# Keypad_Board.net
KiCad netlist of a schematic drawn in EAGLE
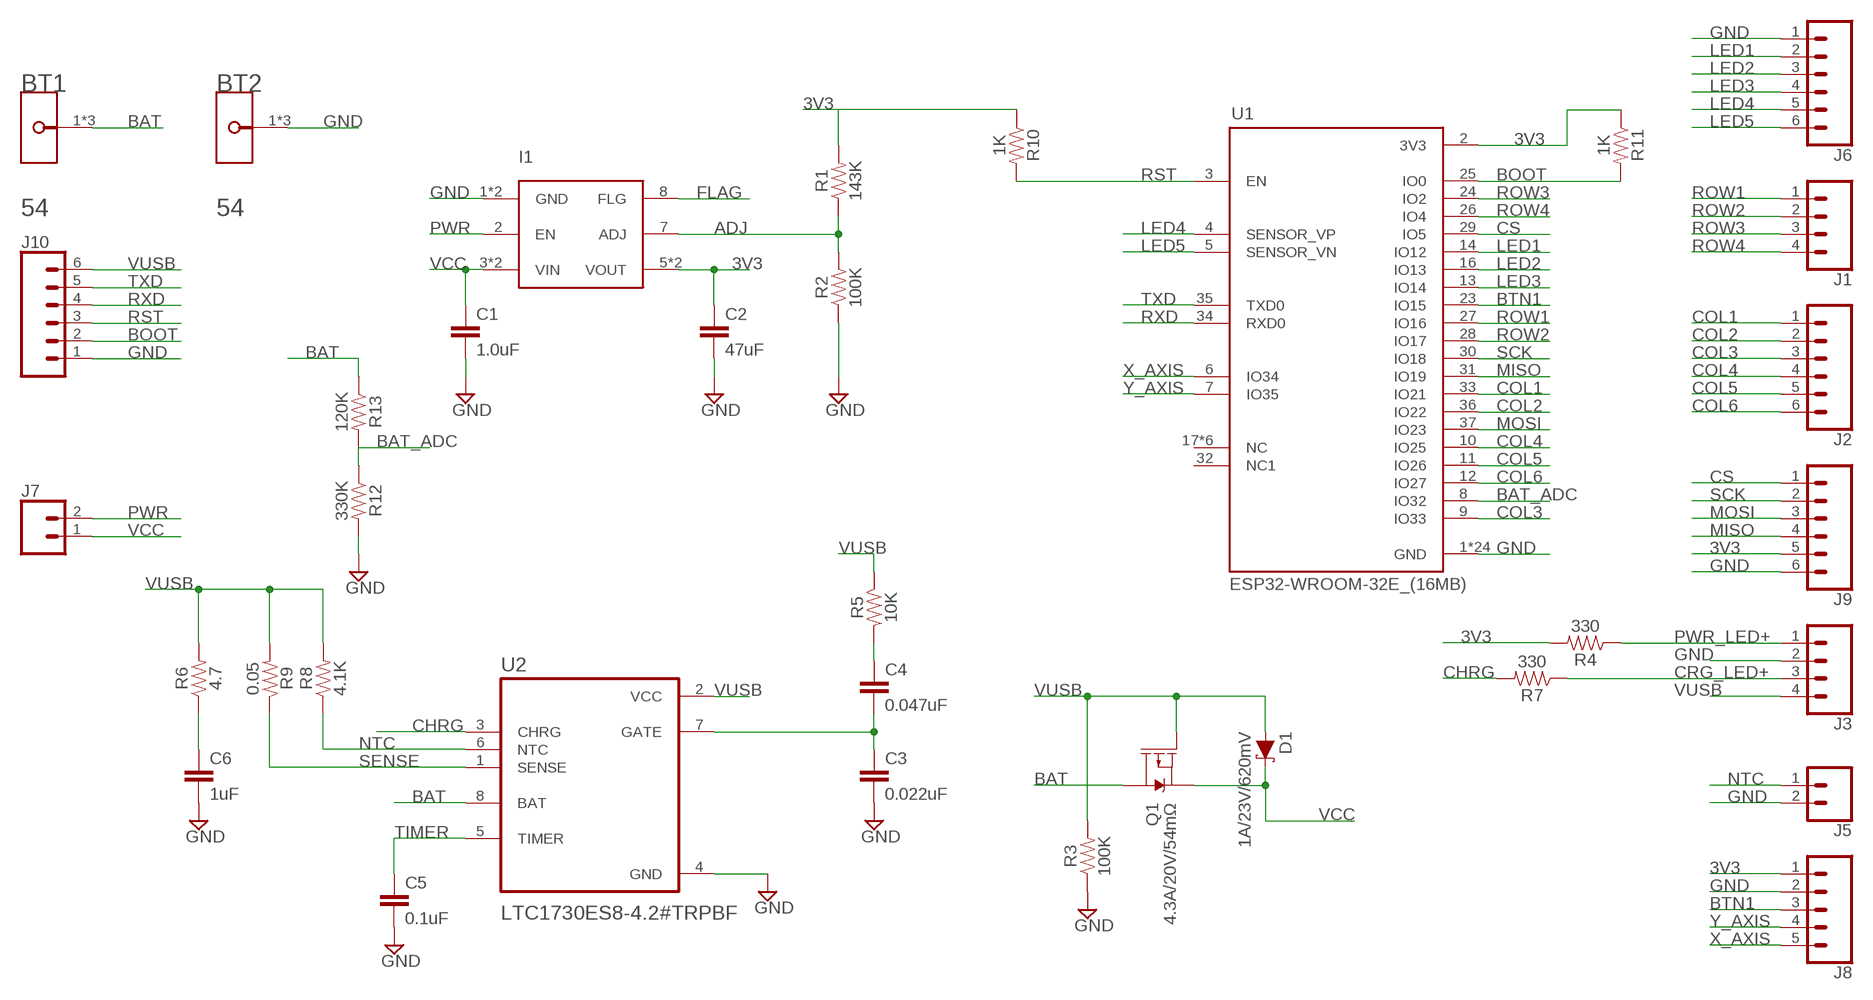
[diagram p0: schematic, sheet 1]

(export (version "E")
  (design (tool "Eeschema 10.0.6"))
  (components
    (comp (ref "BT1")
      (value "KEYSTONE_54KEYSTONE_54_0_0")
      (footprint "eagle-import:KEYSTONE_54_0")
      (fields
        (field (name "DIGIKEY_PART_NUMBER") "36-54-ND")
        (field (name "MF") "Keystone")
        (field (name "MOUSER_PART_NUMBER") "534-54")
      )
      (libsource (lib "eagle-import") (part "KEYSTONE_54KEYSTONE_54_0_0"))
    )
    (comp (ref "BT2")
      (value "KEYSTONE_54KEYSTONE_54_0_0")
      (footprint "eagle-import:KEYSTONE_54_0")
      (fields
        (field (name "DIGIKEY_PART_NUMBER") "36-54-ND")
        (field (name "MF") "Keystone")
        (field (name "MOUSER_PART_NUMBER") "534-54")
      )
      (libsource (lib "eagle-import") (part "KEYSTONE_54KEYSTONE_54_0_0"))
    )
    (comp (ref "C1")
      (value "1.0uF")
      (footprint "eagle-import:1206")
      (libsource (lib "eagle-import") (part "1.0UF-1206-50V-10%"))
    )
    (comp (ref "C2")
      (value "47uF")
      (footprint "eagle-import:1206")
      (libsource (lib "eagle-import") (part "4.7UF-1206-16V-(+80/-20%)"))
    )
    (comp (ref "C3")
      (value "0.022uF")
      (footprint "eagle-import:0603")
      (libsource (lib "eagle-import") (part "0.22UF-0603-50V-(-20/+80%)"))
    )
    (comp (ref "C4")
      (value "0.047uF")
      (footprint "eagle-import:0603")
      (libsource (lib "eagle-import") (part "0.22UF-0603-50V-(-20/+80%)"))
    )
    (comp (ref "C5")
      (value "0.1uF")
      (footprint "eagle-import:0603")
      (libsource (lib "eagle-import") (part "0.22UF-0603-50V-(-20/+80%)"))
    )
    (comp (ref "C6")
      (value "1uF")
      (footprint "eagle-import:0603")
      (libsource (lib "eagle-import") (part "0.22UF-0603-50V-(-20/+80%)"))
    )
    (comp (ref "D1")
      (value "1A/23V/620mV")
      (footprint "eagle-import:SOD-323")
      (libsource (lib "eagle-import") (part "DIODE-SCHOTTKY-BAT20J"))
    )
    (comp (ref "I1")
      (value "MIC37303")
      (footprint "eagle-import:SOIC8")
      (libsource (lib "eagle-import") (part "MIC37303"))
    )
    (comp (ref "J1")
      (value "CONN_04")
      (footprint "eagle-import:1X04")
      (libsource (lib "eagle-import") (part "CONN_04"))
    )
    (comp (ref "J2")
      (value "CONN_06LOCK")
      (footprint "eagle-import:1X06_LOCK")
      (libsource (lib "eagle-import") (part "CONN_06LOCK"))
    )
    (comp (ref "J3")
      (value "CONN_04")
      (footprint "eagle-import:1X04")
      (libsource (lib "eagle-import") (part "CONN_04"))
    )
    (comp (ref "J5")
      (value "CONN_02")
      (footprint "eagle-import:1X02")
      (libsource (lib "eagle-import") (part "CONN_02"))
    )
    (comp (ref "J6")
      (value "CONN_06LOCK")
      (footprint "eagle-import:1X06_LOCK")
      (libsource (lib "eagle-import") (part "CONN_06LOCK"))
    )
    (comp (ref "J7")
      (value "CONN_02")
      (footprint "eagle-import:1X02")
      (libsource (lib "eagle-import") (part "CONN_02"))
    )
    (comp (ref "J8")
      (value "CONN_05")
      (footprint "eagle-import:1X05")
      (libsource (lib "eagle-import") (part "CONN_05"))
    )
    (comp (ref "J9")
      (value "CONN_06LOCK")
      (footprint "eagle-import:1X06_LOCK")
      (libsource (lib "eagle-import") (part "CONN_06LOCK"))
    )
    (comp (ref "J10")
      (value "CONN_06LOCK")
      (footprint "eagle-import:1X06_LOCK")
      (libsource (lib "eagle-import") (part "CONN_06LOCK"))
    )
    (comp (ref "Q1")
      (value "4.3A/20V/54mΩ")
      (footprint "eagle-import:SOT23-3")
      (libsource (lib "eagle-import") (part "MOSFET_PCH-IRLML2244"))
    )
    (comp (ref "R1")
      (value "143K")
      (footprint "eagle-import:1206")
      (libsource (lib "eagle-import") (part "RESISTOR1206"))
    )
    (comp (ref "R2")
      (value "100K")
      (footprint "eagle-import:1206")
      (libsource (lib "eagle-import") (part "RESISTOR1206"))
    )
    (comp (ref "R3")
      (value "100K")
      (footprint "eagle-import:1206")
      (libsource (lib "eagle-import") (part "RESISTOR1206"))
    )
    (comp (ref "R4")
      (value "330")
      (footprint "eagle-import:0805")
      (libsource (lib "eagle-import") (part "0.22OHM-0805-1/4W-1%"))
    )
    (comp (ref "R5")
      (value "10K")
      (footprint "eagle-import:0805")
      (libsource (lib "eagle-import") (part "0.22OHM-0805-1/4W-1%"))
    )
    (comp (ref "R6")
      (value "4.7")
      (footprint "eagle-import:0603")
      (libsource (lib "eagle-import") (part "0.05OHM-0603-1/5W-1%"))
    )
    (comp (ref "R7")
      (value "330")
      (footprint "eagle-import:0805")
      (libsource (lib "eagle-import") (part "0.22OHM-0805-1/4W-1%"))
    )
    (comp (ref "R8")
      (value "4.1K")
      (footprint "eagle-import:0603")
      (libsource (lib "eagle-import") (part "0.05OHM-0603-1/5W-1%"))
    )
    (comp (ref "R9")
      (value "0.05")
      (footprint "eagle-import:0603")
      (libsource (lib "eagle-import") (part "0.05OHM-0603-1/5W-1%"))
    )
    (comp (ref "R10")
      (value "1K")
      (footprint "eagle-import:0805")
      (libsource (lib "eagle-import") (part "0.22OHM-0805-1/4W-1%"))
    )
    (comp (ref "R11")
      (value "1K")
      (footprint "eagle-import:0805")
      (libsource (lib "eagle-import") (part "0.22OHM-0805-1/4W-1%"))
    )
    (comp (ref "R12")
      (value "330K")
      (footprint "eagle-import:0805")
      (libsource (lib "eagle-import") (part "0.22OHM-0805-1/4W-1%"))
    )
    (comp (ref "R13")
      (value "120K")
      (footprint "eagle-import:0805")
      (libsource (lib "eagle-import") (part "0.22OHM-0805-1/4W-1%"))
    )
    (comp (ref "U1")
      (value "ESP32-WROOM-32E_(16MB)")
      (footprint "eagle-import:MODULE_ESP32-WROOM-32E_(16MB)")
      (fields (field (name "MF") "Espressif Systems") (field (name "MP") "ESP32-WROOM-32E (16MB)"))
      (libsource (lib "eagle-import") (part "ESP32-WROOM-32E_(16MB)"))
    )
    (comp (ref "U2")
      (value "LTC1730ES8-4.2#TRPBF")
      (footprint "eagle-import:SO-8_S")
      (fields (field (name "MF") "Analog Devices"))
      (libsource (lib "eagle-import") (part "LTC1730ES8-4.2#TRPBF"))
    )
  )
  (nets
    (net (code "1") (name "/3V3") (class "Default")
      (node (ref "C2") (pin "1") (pinfunction "1_1") (pintype "passive"))
      (node (ref "I1") (pin "5") (pinfunction "VOUT_5") (pintype "output"))
      (node (ref "I1") (pin "6") (pinfunction "VOUT_6") (pintype "output"))
      (node (ref "J8") (pin "1") (pinfunction "1_1") (pintype "passive"))
      (node (ref "J9") (pin "5") (pinfunction "5_5") (pintype "passive"))
      (node (ref "R1") (pin "2") (pinfunction "2_2") (pintype "passive"))
      (node (ref "R10") (pin "1") (pinfunction "1_1") (pintype "passive"))
      (node (ref "R11") (pin "1") (pinfunction "1_1") (pintype "passive"))
      (node (ref "R4") (pin "2") (pinfunction "2_2") (pintype "passive"))
      (node (ref "U1") (pin "2") (pinfunction "3V3_2") (pintype "power_in"))
    )
    (net (code "2") (name "/ADJ") (class "Default")
      (node (ref "I1") (pin "7") (pinfunction "ADJ_7") (pintype "input"))
      (node (ref "R1") (pin "1") (pinfunction "1_1") (pintype "passive"))
      (node (ref "R2") (pin "2") (pinfunction "2_2") (pintype "passive"))
    )
    (net (code "3") (name "/BAT") (class "Default")
      (node (ref "BT1") (pin "1") (pinfunction "1_1") (pintype "power_in"))
      (node (ref "BT1") (pin "1-2") (pinfunction "1_1-2") (pintype "power_in"))
      (node (ref "BT1") (pin "1-3") (pinfunction "1_1-3") (pintype "power_in"))
      (node (ref "Q1") (pin "3") (pinfunction "D_3") (pintype "bidirectional"))
      (node (ref "R13") (pin "1") (pinfunction "1_1") (pintype "passive"))
      (node (ref "U2") (pin "8") (pinfunction "BAT_8") (pintype "bidirectional"))
    )
    (net (code "4") (name "/BAT_ADC") (class "Default")
      (node (ref "R12") (pin "1") (pinfunction "1_1") (pintype "passive"))
      (node (ref "R13") (pin "2") (pinfunction "2_2") (pintype "passive"))
      (node (ref "U1") (pin "8") (pinfunction "IO32_8") (pintype "bidirectional"))
    )
    (net (code "5") (name "/BOOT") (class "Default")
      (node (ref "J10") (pin "2") (pinfunction "2_2") (pintype "passive"))
      (node (ref "R11") (pin "2") (pinfunction "2_2") (pintype "passive"))
      (node (ref "U1") (pin "25") (pinfunction "IO0_25") (pintype "bidirectional"))
    )
    (net (code "6") (name "/BTN1") (class "Default")
      (node (ref "J8") (pin "3") (pinfunction "3_3") (pintype "passive"))
      (node (ref "U1") (pin "23") (pinfunction "IO15_23") (pintype "bidirectional"))
    )
    (net (code "7") (name "/CHRG") (class "Default")
      (node (ref "R7") (pin "2") (pinfunction "2_2") (pintype "passive"))
      (node (ref "U2") (pin "3") (pinfunction "CHRG_3") (pintype "input"))
    )
    (net (code "8") (name "/COL1") (class "Default")
      (node (ref "J2") (pin "1") (pinfunction "1_1") (pintype "passive"))
      (node (ref "U1") (pin "33") (pinfunction "IO21_33") (pintype "bidirectional"))
    )
    (net (code "9") (name "/COL2") (class "Default")
      (node (ref "J2") (pin "2") (pinfunction "2_2") (pintype "passive"))
      (node (ref "U1") (pin "36") (pinfunction "IO22_36") (pintype "bidirectional"))
    )
    (net (code "10") (name "/COL3") (class "Default")
      (node (ref "J2") (pin "3") (pinfunction "3_3") (pintype "passive"))
      (node (ref "U1") (pin "9") (pinfunction "IO33_9") (pintype "bidirectional"))
    )
    (net (code "11") (name "/COL4") (class "Default")
      (node (ref "J2") (pin "4") (pinfunction "4_4") (pintype "passive"))
      (node (ref "U1") (pin "10") (pinfunction "IO25_10") (pintype "bidirectional"))
    )
    (net (code "12") (name "/COL5") (class "Default")
      (node (ref "J2") (pin "5") (pinfunction "5_5") (pintype "passive"))
      (node (ref "U1") (pin "11") (pinfunction "IO26_11") (pintype "bidirectional"))
    )
    (net (code "13") (name "/COL6") (class "Default")
      (node (ref "J2") (pin "6") (pinfunction "6_6") (pintype "passive"))
      (node (ref "U1") (pin "12") (pinfunction "IO27_12") (pintype "bidirectional"))
    )
    (net (code "14") (name "/CRG_LED+") (class "Default")
      (node (ref "J3") (pin "3") (pinfunction "3_3") (pintype "passive"))
      (node (ref "R7") (pin "1") (pinfunction "1_1") (pintype "passive"))
    )
    (net (code "15") (name "/CS") (class "Default")
      (node (ref "J9") (pin "1") (pinfunction "1_1") (pintype "passive"))
      (node (ref "U1") (pin "29") (pinfunction "IO5_29") (pintype "bidirectional"))
    )
    (net (code "16") (name "/FLAG") (class "Default")
      (node (ref "I1") (pin "8") (pinfunction "FLG_8") (pintype "output"))
    )
    (net (code "17") (name "/LED1") (class "Default")
      (node (ref "J6") (pin "2") (pinfunction "2_2") (pintype "passive"))
      (node (ref "U1") (pin "14") (pinfunction "IO12_14") (pintype "bidirectional"))
    )
    (net (code "18") (name "/LED2") (class "Default")
      (node (ref "J6") (pin "3") (pinfunction "3_3") (pintype "passive"))
      (node (ref "U1") (pin "16") (pinfunction "IO13_16") (pintype "bidirectional"))
    )
    (net (code "19") (name "/LED3") (class "Default")
      (node (ref "J6") (pin "4") (pinfunction "4_4") (pintype "passive"))
      (node (ref "U1") (pin "13") (pinfunction "IO14_13") (pintype "bidirectional"))
    )
    (net (code "20") (name "/LED4") (class "Default")
      (node (ref "J6") (pin "5") (pinfunction "5_5") (pintype "passive"))
      (node (ref "U1") (pin "4") (pinfunction "SENSOR_VP_4") (pintype "input"))
    )
    (net (code "21") (name "/LED5") (class "Default")
      (node (ref "J6") (pin "6") (pinfunction "6_6") (pintype "passive"))
      (node (ref "U1") (pin "5") (pinfunction "SENSOR_VN_5") (pintype "input"))
    )
    (net (code "22") (name "/MISO") (class "Default")
      (node (ref "J9") (pin "4") (pinfunction "4_4") (pintype "passive"))
      (node (ref "U1") (pin "31") (pinfunction "IO19_31") (pintype "bidirectional"))
    )
    (net (code "23") (name "/MOSI") (class "Default")
      (node (ref "J9") (pin "3") (pinfunction "3_3") (pintype "passive"))
      (node (ref "U1") (pin "37") (pinfunction "IO23_37") (pintype "bidirectional"))
    )
    (net (code "24") (name "/NTC") (class "Default")
      (node (ref "J5") (pin "1") (pinfunction "1_1") (pintype "passive"))
      (node (ref "R8") (pin "1") (pinfunction "1_1") (pintype "passive"))
      (node (ref "U2") (pin "6") (pinfunction "NTC_6") (pintype "input"))
    )
    (net (code "25") (name "/PWR") (class "Default")
      (node (ref "I1") (pin "2") (pinfunction "EN_2") (pintype "input"))
      (node (ref "J7") (pin "2") (pinfunction "2_2") (pintype "passive"))
    )
    (net (code "26") (name "/PWR_LED+") (class "Default")
      (node (ref "J3") (pin "1") (pinfunction "1_1") (pintype "passive"))
      (node (ref "R4") (pin "1") (pinfunction "1_1") (pintype "passive"))
    )
    (net (code "27") (name "/ROW1") (class "Default")
      (node (ref "J1") (pin "1") (pinfunction "1_1") (pintype "passive"))
      (node (ref "U1") (pin "27") (pinfunction "IO16_27") (pintype "bidirectional"))
    )
    (net (code "28") (name "/ROW2") (class "Default")
      (node (ref "J1") (pin "2") (pinfunction "2_2") (pintype "passive"))
      (node (ref "U1") (pin "28") (pinfunction "IO17_28") (pintype "bidirectional"))
    )
    (net (code "29") (name "/ROW3") (class "Default")
      (node (ref "J1") (pin "3") (pinfunction "3_3") (pintype "passive"))
      (node (ref "U1") (pin "24") (pinfunction "IO2_24") (pintype "bidirectional"))
    )
    (net (code "30") (name "/ROW4") (class "Default")
      (node (ref "J1") (pin "4") (pinfunction "4_4") (pintype "passive"))
      (node (ref "U1") (pin "26") (pinfunction "IO4_26") (pintype "bidirectional"))
    )
    (net (code "31") (name "/RST") (class "Default")
      (node (ref "J10") (pin "3") (pinfunction "3_3") (pintype "passive"))
      (node (ref "R10") (pin "2") (pinfunction "2_2") (pintype "passive"))
      (node (ref "U1") (pin "3") (pinfunction "EN_3") (pintype "input"))
    )
    (net (code "32") (name "/RXD") (class "Default")
      (node (ref "J10") (pin "4") (pinfunction "4_4") (pintype "passive"))
      (node (ref "U1") (pin "34") (pinfunction "RXD0_34") (pintype "bidirectional"))
    )
    (net (code "33") (name "/SCK") (class "Default")
      (node (ref "J9") (pin "2") (pinfunction "2_2") (pintype "passive"))
      (node (ref "U1") (pin "30") (pinfunction "IO18_30") (pintype "bidirectional"))
    )
    (net (code "34") (name "/SENSE") (class "Default")
      (node (ref "R9") (pin "1") (pinfunction "1_1") (pintype "passive"))
      (node (ref "U2") (pin "1") (pinfunction "SENSE_1") (pintype "input"))
    )
    (net (code "35") (name "/TIMER") (class "Default")
      (node (ref "C5") (pin "1") (pinfunction "1_1") (pintype "passive"))
      (node (ref "U2") (pin "5") (pinfunction "TIMER_5") (pintype "bidirectional"))
    )
    (net (code "36") (name "/TXD") (class "Default")
      (node (ref "J10") (pin "5") (pinfunction "5_5") (pintype "passive"))
      (node (ref "U1") (pin "35") (pinfunction "TXD0_35") (pintype "bidirectional"))
    )
    (net (code "37") (name "/VCC") (class "Default")
      (node (ref "C1") (pin "1") (pinfunction "1_1") (pintype "passive"))
      (node (ref "D1") (pin "C") (pinfunction "C_C") (pintype "passive"))
      (node (ref "I1") (pin "3") (pinfunction "VIN_3") (pintype "input"))
      (node (ref "I1") (pin "4") (pinfunction "VIN_4") (pintype "input"))
      (node (ref "J7") (pin "1") (pinfunction "1_1") (pintype "passive"))
      (node (ref "Q1") (pin "2") (pinfunction "S_2") (pintype "bidirectional"))
    )
    (net (code "38") (name "/VUSB") (class "Default")
      (node (ref "D1") (pin "A") (pinfunction "A_A") (pintype "passive"))
      (node (ref "J10") (pin "6") (pinfunction "6_6") (pintype "passive"))
      (node (ref "J3") (pin "4") (pinfunction "4_4") (pintype "passive"))
      (node (ref "Q1") (pin "1") (pinfunction "G_1") (pintype "bidirectional"))
      (node (ref "R3") (pin "2") (pinfunction "2_2") (pintype "passive"))
      (node (ref "R5") (pin "1") (pinfunction "1_1") (pintype "passive"))
      (node (ref "R6") (pin "2") (pinfunction "2_2") (pintype "passive"))
      (node (ref "R8") (pin "2") (pinfunction "2_2") (pintype "passive"))
      (node (ref "R9") (pin "2") (pinfunction "2_2") (pintype "passive"))
      (node (ref "U2") (pin "2") (pinfunction "VCC_2") (pintype "power_in"))
    )
    (net (code "39") (name "/X_AXIS") (class "Default")
      (node (ref "J8") (pin "5") (pinfunction "5_5") (pintype "passive"))
      (node (ref "U1") (pin "6") (pinfunction "IO34_6") (pintype "input"))
    )
    (net (code "40") (name "/Y_AXIS") (class "Default")
      (node (ref "J8") (pin "4") (pinfunction "4_4") (pintype "passive"))
      (node (ref "U1") (pin "7") (pinfunction "IO35_7") (pintype "input"))
    )
    (net (code "41") (name "GND") (class "Default")
      (node (ref "BT2") (pin "1") (pinfunction "1_1") (pintype "power_in"))
      (node (ref "BT2") (pin "1-2") (pinfunction "1_1-2") (pintype "power_in"))
      (node (ref "BT2") (pin "1-3") (pinfunction "1_1-3") (pintype "power_in"))
      (node (ref "C1") (pin "2") (pinfunction "2_2") (pintype "passive"))
      (node (ref "C2") (pin "2") (pinfunction "2_2") (pintype "passive"))
      (node (ref "C3") (pin "2") (pinfunction "2_2") (pintype "passive"))
      (node (ref "C5") (pin "2") (pinfunction "2_2") (pintype "passive"))
      (node (ref "C6") (pin "2") (pinfunction "2_2") (pintype "passive"))
      (node (ref "I1") (pin "1") (pinfunction "GND_1") (pintype "power_in"))
      (node (ref "I1") (pin "9") (pinfunction "GND_9") (pintype "power_in"))
      (node (ref "J10") (pin "1") (pinfunction "1_1") (pintype "passive"))
      (node (ref "J3") (pin "2") (pinfunction "2_2") (pintype "passive"))
      (node (ref "J5") (pin "2") (pinfunction "2_2") (pintype "passive"))
      (node (ref "J6") (pin "1") (pinfunction "1_1") (pintype "passive"))
      (node (ref "J8") (pin "2") (pinfunction "2_2") (pintype "passive"))
      (node (ref "J9") (pin "6") (pinfunction "6_6") (pintype "passive"))
      (node (ref "R12") (pin "2") (pinfunction "2_2") (pintype "passive"))
      (node (ref "R2") (pin "1") (pinfunction "1_1") (pintype "passive"))
      (node (ref "R3") (pin "1") (pinfunction "1_1") (pintype "passive"))
      (node (ref "U1") (pin "1") (pinfunction "GND_1") (pintype "power_in"))
      (node (ref "U1") (pin "15") (pinfunction "GND_15") (pintype "power_in"))
      (node (ref "U1") (pin "38") (pinfunction "GND_38") (pintype "power_in"))
      (node (ref "U1") (pin "39_1") (pinfunction "GND_39_1") (pintype "power_in"))
      (node (ref "U1") (pin "39_10") (pinfunction "GND_39_10") (pintype "power_in"))
      (node (ref "U1") (pin "39_11") (pinfunction "GND_39_11") (pintype "power_in"))
      (node (ref "U1") (pin "39_12") (pinfunction "GND_39_12") (pintype "power_in"))
      (node (ref "U1") (pin "39_13") (pinfunction "GND_39_13") (pintype "power_in"))
      (node (ref "U1") (pin "39_14") (pinfunction "GND_39_14") (pintype "power_in"))
      (node (ref "U1") (pin "39_15") (pinfunction "GND_39_15") (pintype "power_in"))
      (node (ref "U1") (pin "39_16") (pinfunction "GND_39_16") (pintype "power_in"))
      (node (ref "U1") (pin "39_17") (pinfunction "GND_39_17") (pintype "power_in"))
      (node (ref "U1") (pin "39_18") (pinfunction "GND_39_18") (pintype "power_in"))
      (node (ref "U1") (pin "39_19") (pinfunction "GND_39_19") (pintype "power_in"))
      (node (ref "U1") (pin "39_2") (pinfunction "GND_39_2") (pintype "power_in"))
      (node (ref "U1") (pin "39_20") (pinfunction "GND_39_20") (pintype "power_in"))
      (node (ref "U1") (pin "39_21") (pinfunction "GND_39_21") (pintype "power_in"))
      (node (ref "U1") (pin "39_3") (pinfunction "GND_39_3") (pintype "power_in"))
      (node (ref "U1") (pin "39_4") (pinfunction "GND_39_4") (pintype "power_in"))
      (node (ref "U1") (pin "39_5") (pinfunction "GND_39_5") (pintype "power_in"))
      (node (ref "U1") (pin "39_6") (pinfunction "GND_39_6") (pintype "power_in"))
      (node (ref "U1") (pin "39_7") (pinfunction "GND_39_7") (pintype "power_in"))
      (node (ref "U1") (pin "39_8") (pinfunction "GND_39_8") (pintype "power_in"))
      (node (ref "U1") (pin "39_9") (pinfunction "GND_39_9") (pintype "power_in"))
      (node (ref "U2") (pin "4") (pinfunction "GND_4") (pintype "power_in"))
    )
    (net (code "42") (name "Net-(C4-Pad1)") (class "Default")
      (node (ref "C4") (pin "1") (pinfunction "1_1") (pintype "passive"))
      (node (ref "R5") (pin "2") (pinfunction "2_2") (pintype "passive"))
    )
    (net (code "43") (name "Net-(C6-Pad1)") (class "Default")
      (node (ref "C6") (pin "1") (pinfunction "1_1") (pintype "passive"))
      (node (ref "R6") (pin "1") (pinfunction "1_1") (pintype "passive"))
    )
    (net (code "44") (name "Net-(U2-GATE)") (class "Default")
      (node (ref "C3") (pin "1") (pinfunction "1_1") (pintype "passive"))
      (node (ref "C4") (pin "2") (pinfunction "2_2") (pintype "passive"))
      (node (ref "U2") (pin "7") (pinfunction "GATE_7") (pintype "output"))
    )
    (net (code "45") (name "unconnected-(U1-NC-Pad17)") (class "Default")
      (node (ref "U1") (pin "17") (pinfunction "NC_17") (pintype "no_connect"))
    )
    (net (code "46") (name "unconnected-(U1-NC-Pad18)") (class "Default")
      (node (ref "U1") (pin "18") (pinfunction "NC_18") (pintype "no_connect"))
    )
    (net (code "47") (name "unconnected-(U1-NC-Pad19)") (class "Default")
      (node (ref "U1") (pin "19") (pinfunction "NC_19") (pintype "no_connect"))
    )
    (net (code "48") (name "unconnected-(U1-NC-Pad20)") (class "Default")
      (node (ref "U1") (pin "20") (pinfunction "NC_20") (pintype "no_connect"))
    )
    (net (code "49") (name "unconnected-(U1-NC-Pad21)") (class "Default")
      (node (ref "U1") (pin "21") (pinfunction "NC_21") (pintype "no_connect"))
    )
    (net (code "50") (name "unconnected-(U1-NC-Pad22)") (class "Default")
      (node (ref "U1") (pin "22") (pinfunction "NC_22") (pintype "no_connect"))
    )
    (net (code "51") (name "unconnected-(U1-NC1-Pad32)") (class "Default")
      (node (ref "U1") (pin "32") (pinfunction "NC1_32") (pintype "no_connect"))
    )
  )
)
